# sd_tos_dip.net
KiCad netlist of a schematic drawn in EAGLE
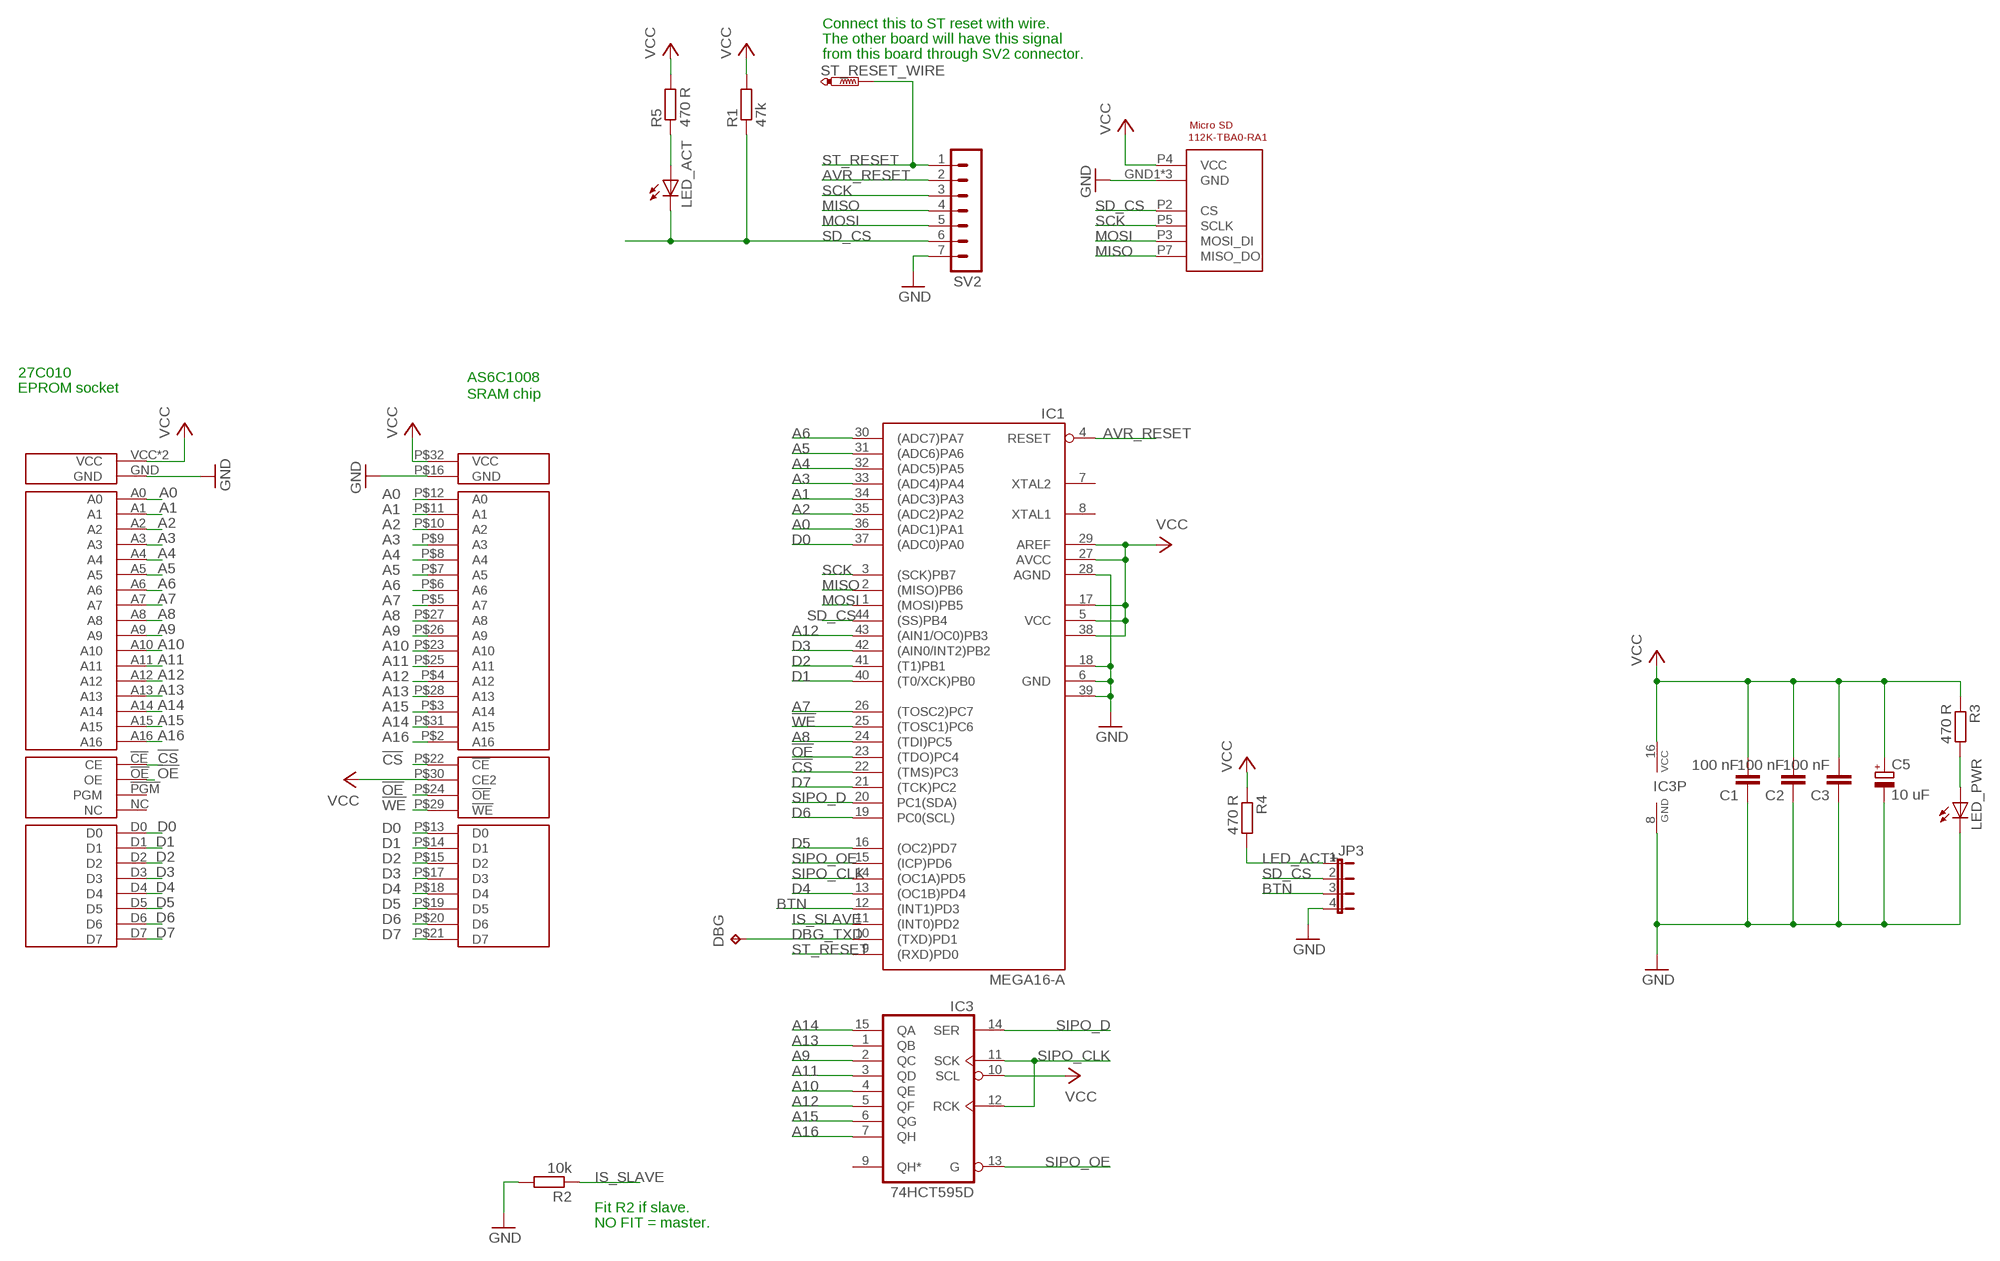
[diagram p0: schematic, sheet 1]

(export (version "E")
  (design (tool "Eeschema 10.0.6"))
  (components
    (comp (ref "C1")
      (value "100 nF")
      (footprint "eagle-import:C0603")
      (libsource (lib "eagle-import") (part "C-EUC0603"))
    )
    (comp (ref "C2")
      (value "100 nF")
      (footprint "eagle-import:C0603")
      (libsource (lib "eagle-import") (part "C-EUC0603"))
    )
    (comp (ref "C3")
      (value "100 nF")
      (footprint "eagle-import:C0603")
      (libsource (lib "eagle-import") (part "C-EUC0603"))
    )
    (comp (ref "C5")
      (value "10 uF")
      (footprint "eagle-import:SANYO-OSCON_SMD_B6")
      (libsource (lib "eagle-import") (part "CPOL-EUSANYO_SMD_B6"))
    )
    (comp (ref "DBG")
      (value "TPB1,27")
      (footprint "eagle-import:B1,27")
      (libsource (lib "eagle-import") (part "TPB1,27"))
    )
    (comp (ref "IC1")
      (value "MEGA16-A")
      (footprint "eagle-import:TQFP44")
      (libsource (lib "eagle-import") (part "MEGA16-A"))
    )
    (comp (ref "IC3")
      (value "74HCT595D")
      (footprint "eagle-import:SO16")
      (libsource (lib "eagle-import") (part "74595DHCT"))
    )
    (comp (ref "JP3")
      (value "JP4E")
      (footprint "eagle-import:JP4")
      (libsource (lib "eagle-import") (part "JP4E"))
    )
    (comp (ref "LED_ACT")
      (value "LEDCHIP-LED0805")
      (footprint "eagle-import:CHIP-LED0805")
      (libsource (lib "eagle-import") (part "LEDCHIP-LED0805"))
    )
    (comp (ref "LED_PWR")
      (value "LEDCHIP-LED0805")
      (footprint "eagle-import:CHIP-LED0805")
      (libsource (lib "eagle-import") (part "LEDCHIP-LED0805"))
    )
    (comp (ref "R1")
      (value "47k")
      (footprint "eagle-import:R0603")
      (libsource (lib "eagle-import") (part "R-EU_R0603"))
    )
    (comp (ref "R2")
      (value "10k")
      (footprint "eagle-import:R0603")
      (libsource (lib "eagle-import") (part "R-EU_R0603"))
    )
    (comp (ref "R3")
      (value "470 R")
      (footprint "eagle-import:R0603")
      (libsource (lib "eagle-import") (part "R-EU_R0603"))
    )
    (comp (ref "R4")
      (value "470 R")
      (footprint "eagle-import:R0603")
      (libsource (lib "eagle-import") (part "R-EU_R0603"))
    )
    (comp (ref "R5")
      (value "470 R")
      (footprint "eagle-import:R0603")
      (libsource (lib "eagle-import") (part "R-EU_R0603"))
    )
    (comp (ref "ST_RESET_WIRE")
      (value "PTR1PAD1-13")
      (footprint "eagle-import:P1-13")
      (libsource (lib "eagle-import") (part "PTR1PAD1-13"))
    )
    (comp (ref "SV2")
      (value "MA07-1")
      (footprint "eagle-import:MA07-1")
      (libsource (lib "eagle-import") (part "MA07-1"))
    )
    (comp (ref "U$1")
      (value "27C010_BOTTOM_ONLY")
      (footprint "eagle-import:DIP32_BOTTOM_ONLY")
      (libsource (lib "eagle-import") (part "27C010_BOTTOM_ONLY"))
    )
    (comp (ref "U$2")
      (value "AS6C1008DIP32")
      (footprint "eagle-import:DIP32")
      (libsource (lib "eagle-import") (part "AS6C1008DIP32"))
    )
    (comp (ref "U$3")
      (value "MICRO_SD")
      (footprint "eagle-import:MICRO_SD")
      (libsource (lib "eagle-import") (part "MICRO_SD"))
    )
  )
  (nets
    (net (code "1") (name "/A0") (class "Default")
      (node (ref "IC1") (pin "36") (pinfunction "(ADC1)PA1_36") (pintype "bidirectional"))
      (node (ref "U$1") (pin "A0") (pinfunction "A0_A0") (pintype "bidirectional"))
      (node (ref "U$2") (pin "P$12") (pinfunction "A0_P$12") (pintype "bidirectional"))
    )
    (net (code "2") (name "/A1") (class "Default")
      (node (ref "IC1") (pin "34") (pinfunction "(ADC3)PA3_34") (pintype "bidirectional"))
      (node (ref "U$1") (pin "A1") (pinfunction "A1_A1") (pintype "bidirectional"))
      (node (ref "U$2") (pin "P$11") (pinfunction "A1_P$11") (pintype "bidirectional"))
    )
    (net (code "3") (name "/A2") (class "Default")
      (node (ref "IC1") (pin "35") (pinfunction "(ADC2)PA2_35") (pintype "bidirectional"))
      (node (ref "U$1") (pin "A2") (pinfunction "A2_A2") (pintype "bidirectional"))
      (node (ref "U$2") (pin "P$10") (pinfunction "A2_P$10") (pintype "bidirectional"))
    )
    (net (code "4") (name "/A3") (class "Default")
      (node (ref "IC1") (pin "33") (pinfunction "(ADC4)PA4_33") (pintype "bidirectional"))
      (node (ref "U$1") (pin "A3") (pinfunction "A3_A3") (pintype "bidirectional"))
      (node (ref "U$2") (pin "P$9") (pinfunction "A3_P$9") (pintype "bidirectional"))
    )
    (net (code "5") (name "/A4") (class "Default")
      (node (ref "IC1") (pin "32") (pinfunction "(ADC5)PA5_32") (pintype "bidirectional"))
      (node (ref "U$1") (pin "A4") (pinfunction "A4_A4") (pintype "bidirectional"))
      (node (ref "U$2") (pin "P$8") (pinfunction "A4_P$8") (pintype "bidirectional"))
    )
    (net (code "6") (name "/A5") (class "Default")
      (node (ref "IC1") (pin "31") (pinfunction "(ADC6)PA6_31") (pintype "bidirectional"))
      (node (ref "U$1") (pin "A5") (pinfunction "A5_A5") (pintype "bidirectional"))
      (node (ref "U$2") (pin "P$7") (pinfunction "A5_P$7") (pintype "bidirectional"))
    )
    (net (code "7") (name "/A6") (class "Default")
      (node (ref "IC1") (pin "30") (pinfunction "(ADC7)PA7_30") (pintype "bidirectional"))
      (node (ref "U$1") (pin "A6") (pinfunction "A6_A6") (pintype "bidirectional"))
      (node (ref "U$2") (pin "P$6") (pinfunction "A6_P$6") (pintype "bidirectional"))
    )
    (net (code "8") (name "/A7") (class "Default")
      (node (ref "IC1") (pin "26") (pinfunction "(TOSC2)PC7_26") (pintype "bidirectional"))
      (node (ref "U$1") (pin "A7") (pinfunction "A7_A7") (pintype "bidirectional"))
      (node (ref "U$2") (pin "P$5") (pinfunction "A7_P$5") (pintype "bidirectional"))
    )
    (net (code "9") (name "/A8") (class "Default")
      (node (ref "IC1") (pin "24") (pinfunction "(TDI)PC5_24") (pintype "bidirectional"))
      (node (ref "U$1") (pin "A8") (pinfunction "A8_A8") (pintype "bidirectional"))
      (node (ref "U$2") (pin "P$27") (pinfunction "A8_P$27") (pintype "bidirectional"))
    )
    (net (code "10") (name "/A9") (class "Default")
      (node (ref "IC3") (pin "2") (pinfunction "QC_2") (pintype "tri_state"))
      (node (ref "U$1") (pin "A9") (pinfunction "A9_A9") (pintype "bidirectional"))
      (node (ref "U$2") (pin "P$26") (pinfunction "A9_P$26") (pintype "bidirectional"))
    )
    (net (code "11") (name "/A10") (class "Default")
      (node (ref "IC3") (pin "4") (pinfunction "QE_4") (pintype "tri_state"))
      (node (ref "U$1") (pin "A10") (pinfunction "A10_A10") (pintype "bidirectional"))
      (node (ref "U$2") (pin "P$23") (pinfunction "A10_P$23") (pintype "bidirectional"))
    )
    (net (code "12") (name "/A11") (class "Default")
      (node (ref "IC3") (pin "3") (pinfunction "QD_3") (pintype "tri_state"))
      (node (ref "U$1") (pin "A11") (pinfunction "A11_A11") (pintype "bidirectional"))
      (node (ref "U$2") (pin "P$25") (pinfunction "A11_P$25") (pintype "bidirectional"))
    )
    (net (code "13") (name "/A12") (class "Default")
      (node (ref "IC1") (pin "43") (pinfunction "(AIN1/OC0)PB3_43") (pintype "bidirectional"))
      (node (ref "IC3") (pin "5") (pinfunction "QF_5") (pintype "tri_state"))
      (node (ref "U$1") (pin "A12") (pinfunction "A12_A12") (pintype "bidirectional"))
      (node (ref "U$2") (pin "P$4") (pinfunction "A12_P$4") (pintype "bidirectional"))
    )
    (net (code "14") (name "/A13") (class "Default")
      (node (ref "IC3") (pin "1") (pinfunction "QB_1") (pintype "tri_state"))
      (node (ref "U$1") (pin "A13") (pinfunction "A13_A13") (pintype "bidirectional"))
      (node (ref "U$2") (pin "P$28") (pinfunction "A13_P$28") (pintype "bidirectional"))
    )
    (net (code "15") (name "/A14") (class "Default")
      (node (ref "IC3") (pin "15") (pinfunction "QA_15") (pintype "tri_state"))
      (node (ref "U$1") (pin "A14") (pinfunction "A14_A14") (pintype "bidirectional"))
      (node (ref "U$2") (pin "P$31") (pinfunction "A15_P$31") (pintype "bidirectional"))
    )
    (net (code "16") (name "/A15") (class "Default")
      (node (ref "IC3") (pin "6") (pinfunction "QG_6") (pintype "tri_state"))
      (node (ref "U$1") (pin "A15") (pinfunction "A15_A15") (pintype "bidirectional"))
      (node (ref "U$2") (pin "P$3") (pinfunction "A14_P$3") (pintype "bidirectional"))
    )
    (net (code "17") (name "/A16") (class "Default")
      (node (ref "IC3") (pin "7") (pinfunction "QH_7") (pintype "tri_state"))
      (node (ref "U$1") (pin "A16") (pinfunction "A16_A16") (pintype "bidirectional"))
      (node (ref "U$2") (pin "P$2") (pinfunction "A16_P$2") (pintype "bidirectional"))
    )
    (net (code "18") (name "/AVR_RESET") (class "Default")
      (node (ref "IC1") (pin "4") (pinfunction "RESET_4") (pintype "input"))
      (node (ref "SV2") (pin "2") (pinfunction "2_2") (pintype "passive"))
    )
    (net (code "19") (name "/BTN") (class "Default")
      (node (ref "IC1") (pin "12") (pinfunction "(INT1)PD3_12") (pintype "bidirectional"))
      (node (ref "JP3") (pin "3") (pinfunction "3_3") (pintype "passive"))
    )
    (net (code "20") (name "/D0") (class "Default")
      (node (ref "IC1") (pin "37") (pinfunction "(ADC0)PA0_37") (pintype "bidirectional"))
      (node (ref "U$1") (pin "D0") (pinfunction "D0_D0") (pintype "bidirectional"))
      (node (ref "U$2") (pin "P$13") (pinfunction "D0_P$13") (pintype "bidirectional"))
    )
    (net (code "21") (name "/D1") (class "Default")
      (node (ref "IC1") (pin "40") (pinfunction "(T0/XCK)PB0_40") (pintype "bidirectional"))
      (node (ref "U$1") (pin "D1") (pinfunction "D1_D1") (pintype "bidirectional"))
      (node (ref "U$2") (pin "P$14") (pinfunction "D1_P$14") (pintype "bidirectional"))
    )
    (net (code "22") (name "/D2") (class "Default")
      (node (ref "IC1") (pin "41") (pinfunction "(T1)PB1_41") (pintype "bidirectional"))
      (node (ref "U$1") (pin "D2") (pinfunction "D2_D2") (pintype "bidirectional"))
      (node (ref "U$2") (pin "P$15") (pinfunction "D2_P$15") (pintype "bidirectional"))
    )
    (net (code "23") (name "/D3") (class "Default")
      (node (ref "IC1") (pin "42") (pinfunction "(AIN0/INT2)PB2_42") (pintype "bidirectional"))
      (node (ref "U$1") (pin "D3") (pinfunction "D3_D3") (pintype "bidirectional"))
      (node (ref "U$2") (pin "P$17") (pinfunction "D3_P$17") (pintype "bidirectional"))
    )
    (net (code "24") (name "/D4") (class "Default")
      (node (ref "IC1") (pin "13") (pinfunction "(OC1B)PD4_13") (pintype "bidirectional"))
      (node (ref "U$1") (pin "D4") (pinfunction "D4_D4") (pintype "bidirectional"))
      (node (ref "U$2") (pin "P$18") (pinfunction "D4_P$18") (pintype "bidirectional"))
    )
    (net (code "25") (name "/D5") (class "Default")
      (node (ref "IC1") (pin "16") (pinfunction "(OC2)PD7_16") (pintype "bidirectional"))
      (node (ref "U$1") (pin "D5") (pinfunction "D5_D5") (pintype "bidirectional"))
      (node (ref "U$2") (pin "P$19") (pinfunction "D5_P$19") (pintype "bidirectional"))
    )
    (net (code "26") (name "/D6") (class "Default")
      (node (ref "IC1") (pin "19") (pinfunction "PC0(SCL)_19") (pintype "bidirectional"))
      (node (ref "U$1") (pin "D6") (pinfunction "D6_D6") (pintype "bidirectional"))
      (node (ref "U$2") (pin "P$20") (pinfunction "D6_P$20") (pintype "bidirectional"))
    )
    (net (code "27") (name "/D7") (class "Default")
      (node (ref "IC1") (pin "21") (pinfunction "(TCK)PC2_21") (pintype "bidirectional"))
      (node (ref "U$1") (pin "D7") (pinfunction "D7_D7") (pintype "bidirectional"))
      (node (ref "U$2") (pin "P$21") (pinfunction "D7_P$21") (pintype "bidirectional"))
    )
    (net (code "28") (name "/DBG_TXD") (class "Default")
      (node (ref "DBG") (pin "TP") (pinfunction "TP_TP") (pintype "input"))
      (node (ref "IC1") (pin "10") (pinfunction "(TXD)PD1_10") (pintype "bidirectional"))
    )
    (net (code "29") (name "/IS_SLAVE") (class "Default")
      (node (ref "IC1") (pin "11") (pinfunction "(INT0)PD2_11") (pintype "bidirectional"))
      (node (ref "R2") (pin "1") (pinfunction "1_1") (pintype "passive"))
    )
    (net (code "30") (name "/LED_ACT+") (class "Default")
      (node (ref "JP3") (pin "1") (pinfunction "1_1") (pintype "passive"))
      (node (ref "R4") (pin "2") (pinfunction "2_2") (pintype "passive"))
    )
    (net (code "31") (name "/MISO") (class "Default")
      (node (ref "IC1") (pin "2") (pinfunction "(MISO)PB6_2") (pintype "bidirectional"))
      (node (ref "SV2") (pin "4") (pinfunction "4_4") (pintype "passive"))
      (node (ref "U$3") (pin "P7") (pinfunction "MISO_DO_P7") (pintype "output"))
    )
    (net (code "32") (name "/MOSI") (class "Default")
      (node (ref "IC1") (pin "1") (pinfunction "(MOSI)PB5_1") (pintype "bidirectional"))
      (node (ref "SV2") (pin "5") (pinfunction "5_5") (pintype "passive"))
      (node (ref "U$3") (pin "P3") (pinfunction "MOSI_DI_P3") (pintype "input"))
    )
    (net (code "33") (name "/SCK") (class "Default")
      (node (ref "IC1") (pin "3") (pinfunction "(SCK)PB7_3") (pintype "bidirectional"))
      (node (ref "SV2") (pin "3") (pinfunction "3_3") (pintype "passive"))
      (node (ref "U$3") (pin "P5") (pinfunction "SCLK_P5") (pintype "input"))
    )
    (net (code "34") (name "/SD_CS") (class "Default")
      (node (ref "IC1") (pin "44") (pinfunction "(SS)PB4_44") (pintype "bidirectional"))
      (node (ref "JP3") (pin "2") (pinfunction "2_2") (pintype "passive"))
      (node (ref "LED_ACT") (pin "C") (pinfunction "C_C") (pintype "passive"))
      (node (ref "R1") (pin "1") (pinfunction "1_1") (pintype "passive"))
      (node (ref "SV2") (pin "6") (pinfunction "6_6") (pintype "passive"))
      (node (ref "U$3") (pin "P2") (pinfunction "CS_P2") (pintype "input"))
    )
    (net (code "35") (name "/SIPO_CLK") (class "Default")
      (node (ref "IC1") (pin "14") (pinfunction "(OC1A)PD5_14") (pintype "bidirectional"))
      (node (ref "IC3") (pin "11") (pinfunction "SCK_11") (pintype "input"))
      (node (ref "IC3") (pin "12") (pinfunction "RCK_12") (pintype "input"))
    )
    (net (code "36") (name "/SIPO_D") (class "Default")
      (node (ref "IC1") (pin "20") (pinfunction "PC1(SDA)_20") (pintype "bidirectional"))
      (node (ref "IC3") (pin "14") (pinfunction "SER_14") (pintype "input"))
    )
    (net (code "37") (name "/SIPO_OE") (class "Default")
      (node (ref "IC1") (pin "15") (pinfunction "(ICP)PD6_15") (pintype "bidirectional"))
      (node (ref "IC3") (pin "13") (pinfunction "G_13") (pintype "input"))
    )
    (net (code "38") (name "/ST_RESET") (class "Default")
      (node (ref "IC1") (pin "9") (pinfunction "(RXD)PD0_9") (pintype "bidirectional"))
      (node (ref "ST_RESET_WIRE") (pin "TP") (pinfunction "TP_TP") (pintype "input"))
      (node (ref "SV2") (pin "1") (pinfunction "1_1") (pintype "passive"))
    )
    (net (code "39") (name "/~{CS}") (class "Default")
      (node (ref "IC1") (pin "22") (pinfunction "(TMS)PC3_22") (pintype "bidirectional"))
      (node (ref "U$1") (pin "!CE") (pinfunction "CE_!CE") (pintype "bidirectional"))
      (node (ref "U$2") (pin "P$22") (pinfunction "~{CE}_P$22") (pintype "bidirectional"))
    )
    (net (code "40") (name "/~{OE}") (class "Default")
      (node (ref "IC1") (pin "23") (pinfunction "(TDO)PC4_23") (pintype "bidirectional"))
      (node (ref "U$1") (pin "!OE") (pinfunction "OE_!OE") (pintype "bidirectional"))
      (node (ref "U$2") (pin "P$24") (pinfunction "~{OE}_P$24") (pintype "bidirectional"))
    )
    (net (code "41") (name "/~{WE}") (class "Default")
      (node (ref "IC1") (pin "25") (pinfunction "(TOSC1)PC6_25") (pintype "bidirectional"))
      (node (ref "U$2") (pin "P$29") (pinfunction "~{WE}_P$29") (pintype "bidirectional"))
    )
    (net (code "42") (name "GND") (class "Default")
      (node (ref "C1") (pin "1") (pinfunction "1_1") (pintype "passive"))
      (node (ref "C2") (pin "1") (pinfunction "1_1") (pintype "passive"))
      (node (ref "C3") (pin "1") (pinfunction "1_1") (pintype "passive"))
      (node (ref "C5") (pin "-") (pinfunction "-_-") (pintype "passive"))
      (node (ref "IC1") (pin "18") (pinfunction "GND1_18") (pintype "power_in"))
      (node (ref "IC1") (pin "28") (pinfunction "AGND_28") (pintype "power_in"))
      (node (ref "IC1") (pin "39") (pinfunction "GND2_39") (pintype "power_in"))
      (node (ref "IC1") (pin "6") (pinfunction "GND_6") (pintype "power_in"))
      (node (ref "IC3") (pin "8") (pinfunction "GND_8") (pintype "power_in"))
      (node (ref "JP3") (pin "4") (pinfunction "4_4") (pintype "passive"))
      (node (ref "LED_PWR") (pin "C") (pinfunction "C_C") (pintype "passive"))
      (node (ref "R2") (pin "2") (pinfunction "2_2") (pintype "passive"))
      (node (ref "SV2") (pin "7") (pinfunction "7_7") (pintype "passive"))
      (node (ref "U$1") (pin "GND") (pinfunction "GND_GND") (pintype "bidirectional"))
      (node (ref "U$2") (pin "P$16") (pinfunction "GND_P$16") (pintype "bidirectional"))
      (node (ref "U$3") (pin "GND1") (pinfunction "GND_GND1") (pintype "power_in"))
      (node (ref "U$3") (pin "GND2") (pinfunction "GND_GND2") (pintype "power_in"))
      (node (ref "U$3") (pin "P6") (pinfunction "GND_P6") (pintype "power_in"))
    )
    (net (code "43") (name "Net-(LED_ACT-PadA)") (class "Default")
      (node (ref "LED_ACT") (pin "A") (pinfunction "A_A") (pintype "passive"))
      (node (ref "R5") (pin "1") (pinfunction "1_1") (pintype "passive"))
    )
    (net (code "44") (name "Net-(LED_PWR-PadA)") (class "Default")
      (node (ref "LED_PWR") (pin "A") (pinfunction "A_A") (pintype "passive"))
      (node (ref "R3") (pin "2") (pinfunction "2_2") (pintype "passive"))
    )
    (net (code "45") (name "VCC") (class "Default")
      (node (ref "C1") (pin "2") (pinfunction "2_2") (pintype "passive"))
      (node (ref "C2") (pin "2") (pinfunction "2_2") (pintype "passive"))
      (node (ref "C3") (pin "2") (pinfunction "2_2") (pintype "passive"))
      (node (ref "C5") (pin "+") (pinfunction "+_+") (pintype "passive"))
      (node (ref "IC1") (pin "17") (pinfunction "VCC1_17") (pintype "power_in"))
      (node (ref "IC1") (pin "27") (pinfunction "AVCC_27") (pintype "power_in"))
      (node (ref "IC1") (pin "29") (pinfunction "AREF_29") (pintype "power_in"))
      (node (ref "IC1") (pin "38") (pinfunction "VCC2_38") (pintype "power_in"))
      (node (ref "IC1") (pin "5") (pinfunction "VCC_5") (pintype "power_in"))
      (node (ref "IC3") (pin "10") (pinfunction "SCL_10") (pintype "input"))
      (node (ref "IC3") (pin "16") (pinfunction "VCC_16") (pintype "power_in"))
      (node (ref "R1") (pin "2") (pinfunction "2_2") (pintype "passive"))
      (node (ref "R3") (pin "1") (pinfunction "1_1") (pintype "passive"))
      (node (ref "R4") (pin "1") (pinfunction "1_1") (pintype "passive"))
      (node (ref "R5") (pin "2") (pinfunction "2_2") (pintype "passive"))
      (node (ref "U$1") (pin "VCC") (pinfunction "VCC_VCC") (pintype "bidirectional"))
      (node (ref "U$1") (pin "VPP") (pinfunction "VCC_VPP") (pintype "bidirectional"))
      (node (ref "U$2") (pin "P$30") (pinfunction "CE2_P$30") (pintype "bidirectional"))
      (node (ref "U$2") (pin "P$32") (pinfunction "VCC_P$32") (pintype "bidirectional"))
      (node (ref "U$3") (pin "P4") (pinfunction "VCC_P4") (pintype "power_in"))
    )
    (net (code "46") (name "unconnected-(IC1-XTAL1-Pad8)") (class "Default")
      (node (ref "IC1") (pin "8") (pinfunction "XTAL1_8") (pintype "bidirectional"))
    )
    (net (code "47") (name "unconnected-(IC1-XTAL2-Pad7)") (class "Default")
      (node (ref "IC1") (pin "7") (pinfunction "XTAL2_7") (pintype "bidirectional"))
    )
    (net (code "48") (name "unconnected-(IC3A-QH*-Pad9)") (class "Default")
      (node (ref "IC3") (pin "9") (pinfunction "QH*_9") (pintype "tri_state"))
    )
    (net (code "49") (name "unconnected-(U$1-PGM-Pad!PGM)") (class "Default")
      (node (ref "U$1") (pin "!PGM") (pinfunction "PGM_!PGM") (pintype "bidirectional"))
    )
    (net (code "50") (name "unconnected-(U$1-PadNC)") (class "Default")
      (node (ref "U$1") (pin "NC") (pinfunction "NC_NC") (pintype "bidirectional"))
    )
  )
)
